# beacon_pcb.net
KiCad netlist of a schematic drawn in Altium Designer
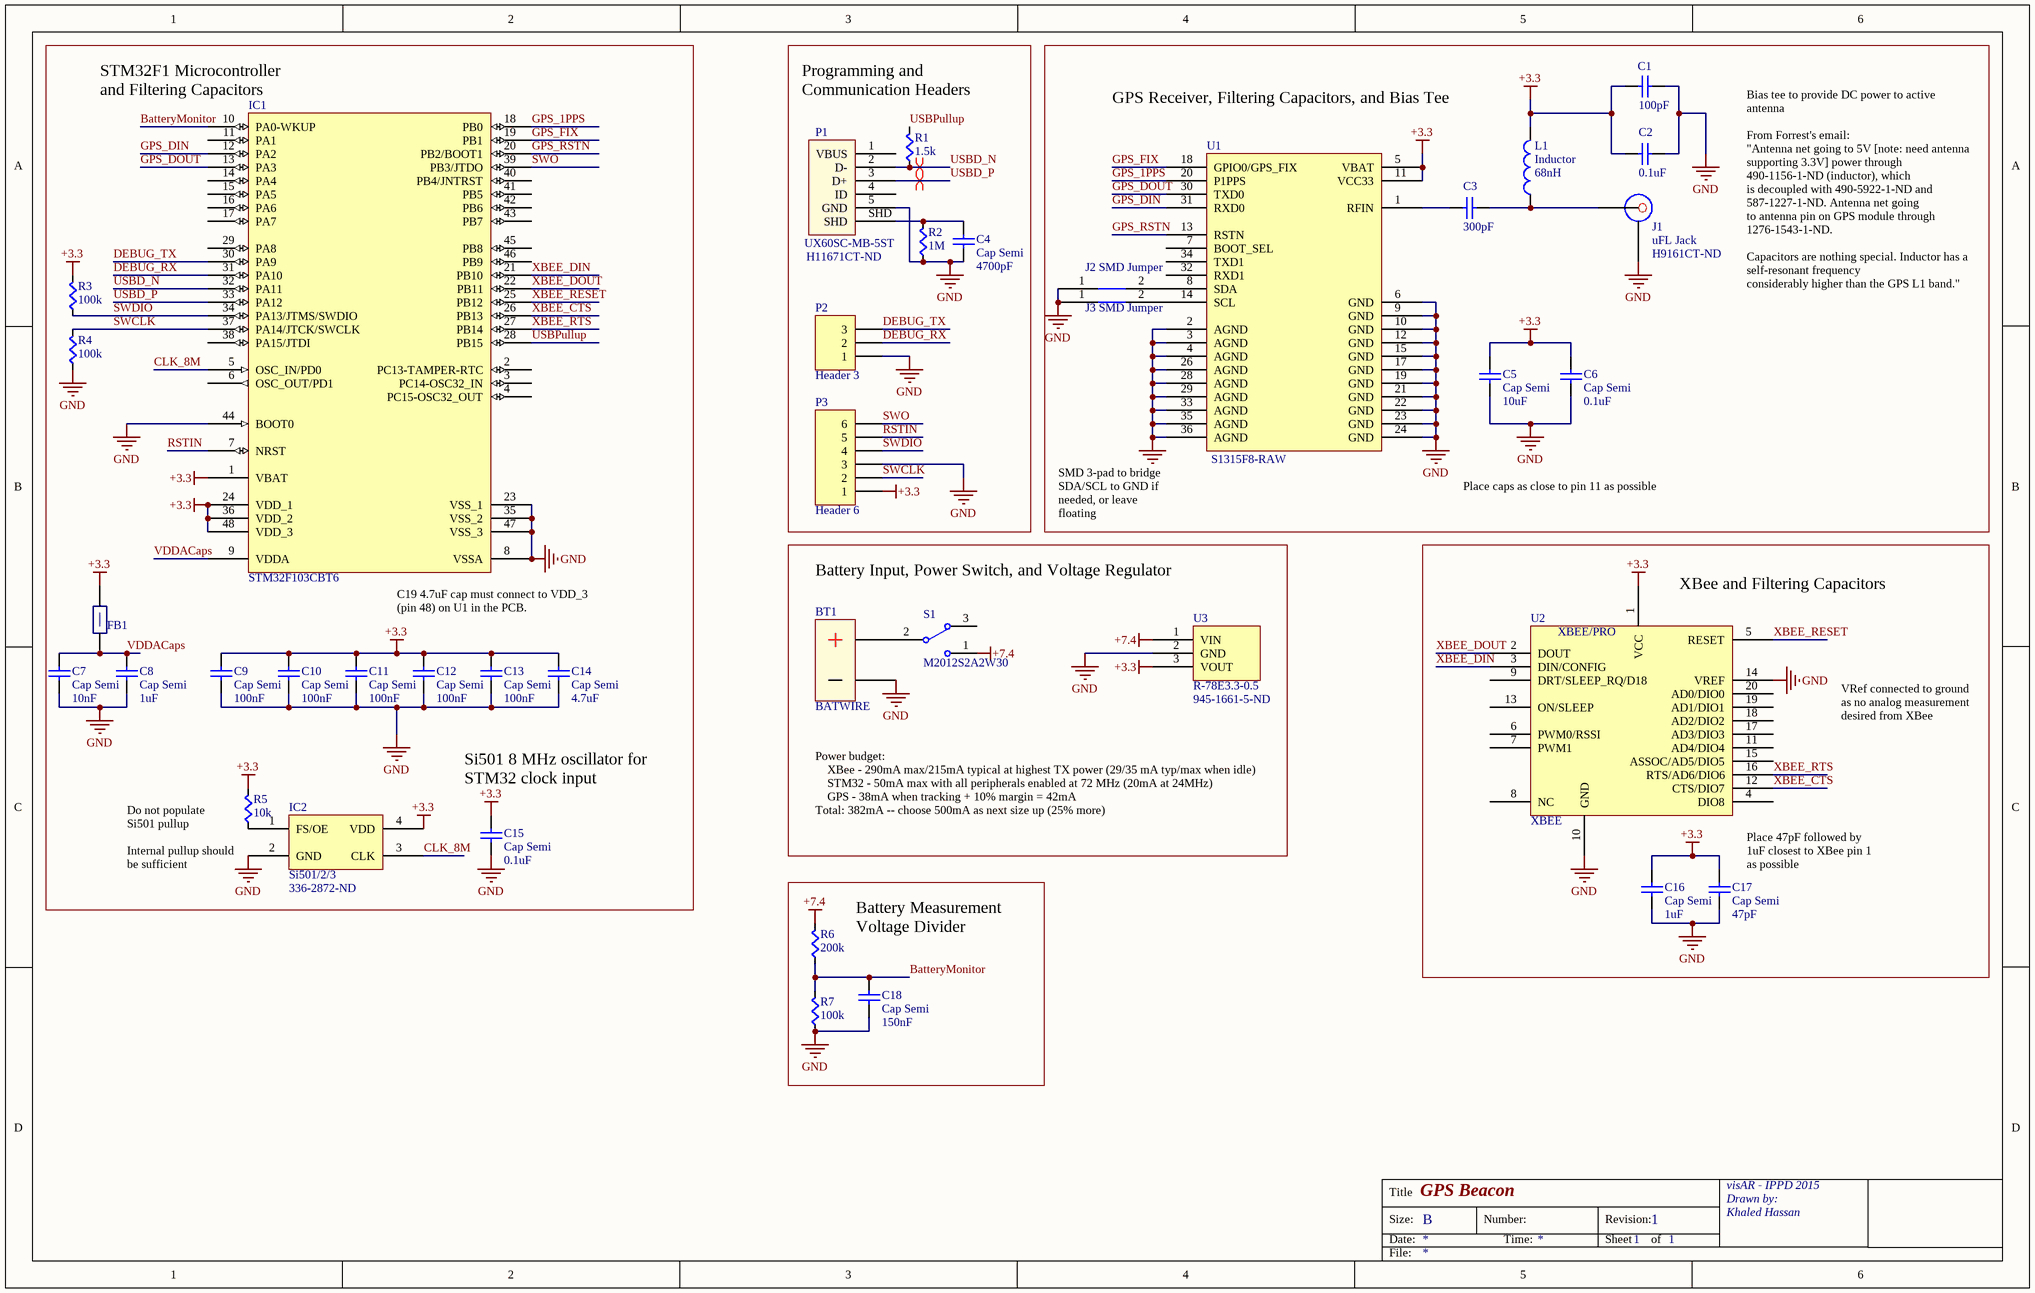
[diagram p0: beacon_pcb.SchDoc]

(export (version "E")
  (design (tool "Eeschema 10.0.6"))
  (components
    (comp (ref "BT1")
      (value "BATWIRE")
      (footprint "BATWIRE12")
      (description "Two large gauge leads soldered directly to the board.")
      (libsource (lib "Connectors") (part "BATWIRE"))
    )
    (comp (ref "C1")
      (value "100pF")
      (footprint "1608[0603]")
      (description "Capacitor (Semiconductor SIM Model)")
      (fields (field (name "Comment") "Cap Semi") (field (name "PUBLISHER") "Altium Limited"))
      (libsource (lib "Miscellaneous Devices") (part "Cap Semi"))
    )
    (comp (ref "C2")
      (value "0.1uF")
      (footprint "1608[0603]")
      (description "Capacitor (Semiconductor SIM Model)")
      (fields (field (name "Comment") "Cap Semi") (field (name "PUBLISHER") "Altium Limited"))
      (libsource (lib "Miscellaneous Devices") (part "Cap Semi"))
    )
    (comp (ref "C3")
      (value "300pF")
      (footprint "1608[0603]")
      (description "Capacitor (Semiconductor SIM Model)")
      (fields (field (name "Comment") "Cap Semi") (field (name "PUBLISHER") "Altium Limited"))
      (libsource (lib "Miscellaneous Devices") (part "Cap Semi"))
    )
    (comp (ref "C4")
      (value "Cap Semi")
      (footprint "1608[0603]")
      (description "Capacitor (Semiconductor SIM Model)")
      (fields (field (name "ALTIUM_VALUE") "4700pF") (field (name "PUBLISHER") "Altium Limited"))
      (libsource (lib "Miscellaneous Devices") (part "Cap Semi"))
    )
    (comp (ref "C5")
      (value "Cap Semi")
      (footprint "1608[0603]")
      (description "Capacitor (Semiconductor SIM Model)")
      (fields (field (name "ALTIUM_VALUE") "10uF") (field (name "PUBLISHER") "Altium Limited"))
      (libsource (lib "Miscellaneous Devices") (part "Cap Semi"))
    )
    (comp (ref "C6")
      (value "Cap Semi")
      (footprint "1608[0603]")
      (description "Capacitor (Semiconductor SIM Model)")
      (fields (field (name "ALTIUM_VALUE") "0.1uF") (field (name "PUBLISHER") "Altium Limited"))
      (libsource (lib "Miscellaneous Devices") (part "Cap Semi"))
    )
    (comp (ref "C7")
      (value "Cap Semi")
      (footprint "1608[0603]")
      (description "Capacitor (Semiconductor SIM Model)")
      (fields (field (name "ALTIUM_VALUE") "10nF") (field (name "PUBLISHER") "Altium Limited"))
      (libsource (lib "Miscellaneous Devices") (part "Cap Semi"))
    )
    (comp (ref "C8")
      (value "Cap Semi")
      (footprint "1608[0603]")
      (description "Capacitor (Semiconductor SIM Model)")
      (fields (field (name "ALTIUM_VALUE") "1uF") (field (name "PUBLISHER") "Altium Limited"))
      (libsource (lib "Miscellaneous Devices") (part "Cap Semi"))
    )
    (comp (ref "C9")
      (value "Cap Semi")
      (footprint "1608[0603]")
      (description "Capacitor (Semiconductor SIM Model)")
      (fields (field (name "ALTIUM_VALUE") "100nF") (field (name "PUBLISHER") "Altium Limited"))
      (libsource (lib "Miscellaneous Devices") (part "Cap Semi"))
    )
    (comp (ref "C10")
      (value "Cap Semi")
      (footprint "1608[0603]")
      (description "Capacitor (Semiconductor SIM Model)")
      (fields (field (name "ALTIUM_VALUE") "100nF") (field (name "PUBLISHER") "Altium Limited"))
      (libsource (lib "Miscellaneous Devices") (part "Cap Semi"))
    )
    (comp (ref "C11")
      (value "Cap Semi")
      (footprint "1608[0603]")
      (description "Capacitor (Semiconductor SIM Model)")
      (fields (field (name "ALTIUM_VALUE") "100nF") (field (name "PUBLISHER") "Altium Limited"))
      (libsource (lib "Miscellaneous Devices") (part "Cap Semi"))
    )
    (comp (ref "C12")
      (value "Cap Semi")
      (footprint "1608[0603]")
      (description "Capacitor (Semiconductor SIM Model)")
      (fields (field (name "ALTIUM_VALUE") "100nF") (field (name "PUBLISHER") "Altium Limited"))
      (libsource (lib "Miscellaneous Devices") (part "Cap Semi"))
    )
    (comp (ref "C13")
      (value "Cap Semi")
      (footprint "1608[0603]")
      (description "Capacitor (Semiconductor SIM Model)")
      (fields (field (name "ALTIUM_VALUE") "100nF") (field (name "PUBLISHER") "Altium Limited"))
      (libsource (lib "Miscellaneous Devices") (part "Cap Semi"))
    )
    (comp (ref "C14")
      (value "Cap Semi")
      (footprint "1608[0603]")
      (description "Capacitor (Semiconductor SIM Model)")
      (fields (field (name "ALTIUM_VALUE") "4.7uF") (field (name "PUBLISHER") "Altium Limited"))
      (libsource (lib "Miscellaneous Devices") (part "Cap Semi"))
    )
    (comp (ref "C15")
      (value "Cap Semi")
      (footprint "1608[0603]")
      (description "Capacitor (Semiconductor SIM Model)")
      (fields (field (name "ALTIUM_VALUE") "0.1uF") (field (name "PUBLISHER") "Altium Limited"))
      (libsource (lib "Miscellaneous Devices") (part "Cap Semi"))
    )
    (comp (ref "C16")
      (value "Cap Semi")
      (footprint "1608[0603]")
      (description "Capacitor (Semiconductor SIM Model)")
      (fields (field (name "ALTIUM_VALUE") "1uF") (field (name "PUBLISHER") "Altium Limited"))
      (libsource (lib "Miscellaneous Devices") (part "Cap Semi"))
    )
    (comp (ref "C17")
      (value "Cap Semi")
      (footprint "1608[0603]")
      (description "Capacitor (Semiconductor SIM Model)")
      (fields (field (name "ALTIUM_VALUE") "47pF") (field (name "PUBLISHER") "Altium Limited"))
      (libsource (lib "Miscellaneous Devices") (part "Cap Semi"))
    )
    (comp (ref "C18")
      (value "Cap Semi")
      (footprint "1608[0603]")
      (description "Capacitor (Semiconductor SIM Model)")
      (fields (field (name "ALTIUM_VALUE") "150nF") (field (name "PUBLISHER") "Altium Limited"))
      (libsource (lib "Miscellaneous Devices") (part "Cap Semi"))
    )
    (comp (ref "FB1")
      (value "FBead")
      (footprint "RES0603")
      (description "Ferrite Bead")
      (libsource (lib "Passives") (part "FBead"))
    )
    (comp (ref "IC1")
      (value "STM32F103CBT6")
      (footprint "STM-LQFP48_N")
      (description "STM32 ARM-based 32-bit MCU with 64 Kbytes Flash, 48-pin LQFP, Industrial Temperature")
      (fields (field (name "PUBLISHER") "Altium Limited"))
      (libsource (lib "ST Microcontroller 32-Bit STM32") (part "STM32F103C8T6"))
    )
    (comp (ref "IC2")
      (value "Si501/2/3")
      (footprint "3.2 x 5 mm 4-pin DFN")
      (fields (field (name "SUPPLIER PART NUMBER 1") "336-2872-ND"))
      (libsource (lib "beacon_pcb") (part "Si501/2/3"))
    )
    (comp (ref "J1")
      (value "uFL Jack")
      (footprint "H9161CT-ND")
      (fields (field (name "SUPPLIER PART NUMBER 1") "H9161CT-ND"))
      (libsource (lib "beacon_pcb") (part "uFL Jack"))
    )
    (comp (ref "J2")
      (value "SMD Jumper")
      (footprint "SMD 2PAD")
      (libsource (lib "beacon_pcb") (part "SMD Jumper"))
    )
    (comp (ref "J3")
      (value "SMD Jumper")
      (footprint "SMD 2PAD")
      (libsource (lib "beacon_pcb") (part "SMD Jumper"))
    )
    (comp (ref "L1")
      (value "Inductor")
      (footprint "0402-A")
      (fields (field (name "ALTIUM_VALUE") "68nH") (field (name "PUBLISHER") "Altium Limited"))
      (libsource (lib "Miscellaneous Devices") (part "Inductor"))
    )
    (comp (ref "P1")
      (value "UX60SC-MB-5ST")
      (footprint "UX60SC-MB-5ST")
      (description "USB Mini B Metal Shield SMT")
      (fields (field (name "SUPPLIER PART NUMBER 1") "H11671CT-ND"))
      (libsource (lib "Connectors") (part "UX60SC-MB-5ST"))
    )
    (comp (ref "P2")
      (value "Header 3")
      (footprint "HDR1X3")
      (description "Header, 3-Pin")
      (fields (field (name "PUBLISHER") "Altium Limited"))
      (libsource (lib "Miscellaneous Connectors") (part "Header 3"))
    )
    (comp (ref "P3")
      (value "Header 6")
      (footprint "HDR1X6")
      (description "Header, 6-Pin")
      (fields (field (name "PUBLISHER") "Altium Limited"))
      (libsource (lib "Miscellaneous Connectors") (part "Header 6"))
    )
    (comp (ref "R1")
      (value "1.5k")
      (footprint "RES0603")
      (fields (field (name "Comment") "Res"))
      (libsource (lib "Passives") (part "Res"))
    )
    (comp (ref "R2")
      (value "1M")
      (footprint "RES0603")
      (fields (field (name "Comment") "Res"))
      (libsource (lib "Passives") (part "Res"))
    )
    (comp (ref "R3")
      (value "100k")
      (footprint "RES0603")
      (fields (field (name "Comment") "Res"))
      (libsource (lib "Passives") (part "Res"))
    )
    (comp (ref "R4")
      (value "100k")
      (footprint "RES0603")
      (fields (field (name "Comment") "Res"))
      (libsource (lib "Passives") (part "Res"))
    )
    (comp (ref "R5")
      (value "10k")
      (footprint "RES0603")
      (fields (field (name "Comment") "Res"))
      (libsource (lib "Passives") (part "Res"))
    )
    (comp (ref "R6")
      (value "200k")
      (footprint "RES0603")
      (fields (field (name "Comment") "Res"))
      (libsource (lib "Passives") (part "Res"))
    )
    (comp (ref "R7")
      (value "100k")
      (footprint "RES0603")
      (fields (field (name "Comment") "Res"))
      (libsource (lib "Passives") (part "Res"))
    )
    (comp (ref "S1")
      (value "M2012S2A2W30")
      (footprint "M2012S2A2W30")
      (description "SPDT Subminiature Toggle Switch, Right Angle Mounting, Vertical Actuation")
      (fields (field (name "PUBLISHER") "Altium Limited"))
      (libsource (lib "Miscellaneous Devices") (part "SW-SPDT"))
    )
    (comp (ref "U1")
      (value "S1315F8-RAW")
      (footprint "S1315F8-RAW")
      (libsource (lib "beacon_pcb") (part "S1315F8-RAW"))
    )
    (comp (ref "U2") (value "XBEE") (footprint "XBEE/PRO") (libsource (lib "ECE Lib") (part "XBEE")))
    (comp (ref "U3")
      (value "R-78E3.3-0.5")
      (footprint "R-78E3.3-0.5")
      (fields (field (name "SUPPLIER PART NUMBER 1") "945-1661-5-ND"))
      (libsource (lib "beacon_pcb") (part "R-78E3.3-0.5"))
    )
  )
  (nets
    (net (code "1") (name "+3.3") (class "Default")
      (node (ref "C1") (pin "2") (pinfunction "2_2") (pintype "passive"))
      (node (ref "C10") (pin "2") (pinfunction "2_2") (pintype "passive"))
      (node (ref "C11") (pin "2") (pinfunction "2_2") (pintype "passive"))
      (node (ref "C12") (pin "2") (pinfunction "2_2") (pintype "passive"))
      (node (ref "C13") (pin "2") (pinfunction "2_2") (pintype "passive"))
      (node (ref "C14") (pin "2") (pinfunction "2_2") (pintype "passive"))
      (node (ref "C15") (pin "2") (pinfunction "2_2") (pintype "passive"))
      (node (ref "C16") (pin "2") (pinfunction "2_2") (pintype "passive"))
      (node (ref "C17") (pin "2") (pinfunction "2_2") (pintype "passive"))
      (node (ref "C2") (pin "2") (pinfunction "2_2") (pintype "passive"))
      (node (ref "C5") (pin "2") (pinfunction "2_2") (pintype "passive"))
      (node (ref "C6") (pin "2") (pinfunction "2_2") (pintype "passive"))
      (node (ref "C9") (pin "2") (pinfunction "2_2") (pintype "passive"))
      (node (ref "FB1") (pin "2") (pinfunction "B_2") (pintype "passive"))
      (node (ref "IC1") (pin "1") (pinfunction "VBAT_1") (pintype "power_in"))
      (node (ref "IC1") (pin "24") (pinfunction "VDD_1_24") (pintype "power_in"))
      (node (ref "IC1") (pin "36") (pinfunction "VDD_2_36") (pintype "power_in"))
      (node (ref "IC1") (pin "48") (pinfunction "VDD_3_48") (pintype "power_in"))
      (node (ref "IC2") (pin "4") (pinfunction "VDD_4") (pintype "passive"))
      (node (ref "L1") (pin "2") (pinfunction "2_2") (pintype "passive"))
      (node (ref "P3") (pin "1") (pinfunction "1_1") (pintype "passive"))
      (node (ref "R3") (pin "1") (pinfunction "A_1") (pintype "passive"))
      (node (ref "R5") (pin "1") (pinfunction "A_1") (pintype "passive"))
      (node (ref "U1") (pin "11") (pinfunction "VCC33_11") (pintype "passive"))
      (node (ref "U1") (pin "5") (pinfunction "VBAT_5") (pintype "passive"))
      (node (ref "U2") (pin "1") (pinfunction "VCC_1") (pintype "passive"))
      (node (ref "U3") (pin "3") (pinfunction "VOUT_3") (pintype "passive"))
    )
    (net (code "2") (name "+7.4") (class "Default")
      (node (ref "R6") (pin "1") (pinfunction "A_1") (pintype "passive"))
      (node (ref "S1") (pin "1") (pinfunction "1_1") (pintype "passive"))
      (node (ref "U3") (pin "1") (pinfunction "VIN_1") (pintype "passive"))
    )
    (net (code "3") (name "/BatteryMonitor") (class "Default")
      (node (ref "C18") (pin "2") (pinfunction "2_2") (pintype "passive"))
      (node (ref "IC1") (pin "10") (pinfunction "PA0-WKUP_10") (pintype "bidirectional"))
      (node (ref "R6") (pin "2") (pinfunction "B_2") (pintype "passive"))
      (node (ref "R7") (pin "1") (pinfunction "A_1") (pintype "passive"))
    )
    (net (code "4") (name "/CLK_8M") (class "Default")
      (node (ref "IC1") (pin "5") (pinfunction "OSC_IN/PD0_5") (pintype "input"))
      (node (ref "IC2") (pin "3") (pinfunction "CLK_3") (pintype "passive"))
    )
    (net (code "5") (name "/DEBUG_RX") (class "Default")
      (node (ref "IC1") (pin "31") (pinfunction "PA10_31") (pintype "bidirectional"))
      (node (ref "P2") (pin "2") (pinfunction "2_2") (pintype "passive"))
    )
    (net (code "6") (name "/DEBUG_TX") (class "Default")
      (node (ref "IC1") (pin "30") (pinfunction "PA9_30") (pintype "bidirectional"))
      (node (ref "P2") (pin "3") (pinfunction "3_3") (pintype "passive"))
    )
    (net (code "7") (name "/GPS_1PPS") (class "Default")
      (node (ref "IC1") (pin "18") (pinfunction "PB0_18") (pintype "bidirectional"))
      (node (ref "U1") (pin "20") (pinfunction "P1PPS_20") (pintype "passive"))
    )
    (net (code "8") (name "/GPS_DIN") (class "Default")
      (node (ref "IC1") (pin "12") (pinfunction "PA2_12") (pintype "bidirectional"))
      (node (ref "U1") (pin "31") (pinfunction "RXD0_31") (pintype "passive"))
    )
    (net (code "9") (name "/GPS_DOUT") (class "Default")
      (node (ref "IC1") (pin "13") (pinfunction "PA3_13") (pintype "bidirectional"))
      (node (ref "U1") (pin "30") (pinfunction "TXD0_30") (pintype "passive"))
    )
    (net (code "10") (name "/GPS_FIX") (class "Default")
      (node (ref "IC1") (pin "19") (pinfunction "PB1_19") (pintype "bidirectional"))
      (node (ref "U1") (pin "18") (pinfunction "GPIO0/GPS_FIX_18") (pintype "passive"))
    )
    (net (code "11") (name "/GPS_RSTN") (class "Default")
      (node (ref "IC1") (pin "20") (pinfunction "PB2/BOOT1_20") (pintype "bidirectional"))
      (node (ref "U1") (pin "13") (pinfunction "RSTN_13") (pintype "passive"))
    )
    (net (code "12") (name "/RSTIN") (class "Default")
      (node (ref "IC1") (pin "7") (pinfunction "NRST_7") (pintype "bidirectional"))
      (node (ref "P3") (pin "5") (pinfunction "5_5") (pintype "passive"))
    )
    (net (code "13") (name "/SWCLK") (class "Default")
      (node (ref "IC1") (pin "37") (pinfunction "PA14/JTCK/SWCLK_37") (pintype "bidirectional"))
      (node (ref "P3") (pin "2") (pinfunction "2_2") (pintype "passive"))
      (node (ref "R4") (pin "1") (pinfunction "A_1") (pintype "passive"))
    )
    (net (code "14") (name "/SWDIO") (class "Default")
      (node (ref "IC1") (pin "34") (pinfunction "PA13/JTMS/SWDIO_34") (pintype "bidirectional"))
      (node (ref "P3") (pin "4") (pinfunction "4_4") (pintype "passive"))
      (node (ref "R3") (pin "2") (pinfunction "B_2") (pintype "passive"))
    )
    (net (code "15") (name "/SWO") (class "Default")
      (node (ref "IC1") (pin "39") (pinfunction "PB3/JTDO_39") (pintype "bidirectional"))
      (node (ref "P3") (pin "6") (pinfunction "6_6") (pintype "passive"))
    )
    (net (code "16") (name "/USBD_N") (class "Default")
      (node (ref "IC1") (pin "32") (pinfunction "PA11_32") (pintype "bidirectional"))
      (node (ref "P1") (pin "2") (pinfunction "D-_2") (pintype "passive"))
      (node (ref "R1") (pin "2") (pinfunction "B_2") (pintype "passive"))
    )
    (net (code "17") (name "/USBD_P") (class "Default")
      (node (ref "IC1") (pin "33") (pinfunction "PA12_33") (pintype "bidirectional"))
      (node (ref "P1") (pin "3") (pinfunction "D+_3") (pintype "passive"))
    )
    (net (code "18") (name "/USBPullup") (class "Default")
      (node (ref "IC1") (pin "28") (pinfunction "PB15_28") (pintype "bidirectional"))
      (node (ref "R1") (pin "1") (pinfunction "A_1") (pintype "passive"))
    )
    (net (code "19") (name "/VDDACaps") (class "Default")
      (node (ref "C7") (pin "2") (pinfunction "2_2") (pintype "passive"))
      (node (ref "C8") (pin "2") (pinfunction "2_2") (pintype "passive"))
      (node (ref "FB1") (pin "1") (pinfunction "A_1") (pintype "passive"))
      (node (ref "IC1") (pin "9") (pinfunction "VDDA_9") (pintype "power_in"))
    )
    (net (code "20") (name "/XBEE_CTS") (class "Default")
      (node (ref "IC1") (pin "26") (pinfunction "PB13_26") (pintype "bidirectional"))
      (node (ref "U2") (pin "12") (pinfunction "CTS/DIO7_12") (pintype "passive"))
    )
    (net (code "21") (name "/XBEE_DIN") (class "Default")
      (node (ref "IC1") (pin "21") (pinfunction "PB10_21") (pintype "bidirectional"))
      (node (ref "U2") (pin "3") (pinfunction "DIN/CONFIG_3") (pintype "passive"))
    )
    (net (code "22") (name "/XBEE_DOUT") (class "Default")
      (node (ref "IC1") (pin "22") (pinfunction "PB11_22") (pintype "bidirectional"))
      (node (ref "U2") (pin "2") (pinfunction "DOUT_2") (pintype "passive"))
    )
    (net (code "23") (name "/XBEE_RESET") (class "Default")
      (node (ref "IC1") (pin "25") (pinfunction "PB12_25") (pintype "bidirectional"))
      (node (ref "U2") (pin "5") (pinfunction "RESET_5") (pintype "passive"))
    )
    (net (code "24") (name "/XBEE_RTS") (class "Default")
      (node (ref "IC1") (pin "27") (pinfunction "PB14_27") (pintype "bidirectional"))
      (node (ref "U2") (pin "16") (pinfunction "RTS/AD6/DIO6_16") (pintype "passive"))
    )
    (net (code "25") (name "GND") (class "Default")
      (node (ref "BT1") (pin "-") (pinfunction "-_-") (pintype "power_in"))
      (node (ref "C1") (pin "1") (pinfunction "1_1") (pintype "passive"))
      (node (ref "C10") (pin "1") (pinfunction "1_1") (pintype "passive"))
      (node (ref "C11") (pin "1") (pinfunction "1_1") (pintype "passive"))
      (node (ref "C12") (pin "1") (pinfunction "1_1") (pintype "passive"))
      (node (ref "C13") (pin "1") (pinfunction "1_1") (pintype "passive"))
      (node (ref "C14") (pin "1") (pinfunction "1_1") (pintype "passive"))
      (node (ref "C15") (pin "1") (pinfunction "1_1") (pintype "passive"))
      (node (ref "C16") (pin "1") (pinfunction "1_1") (pintype "passive"))
      (node (ref "C17") (pin "1") (pinfunction "1_1") (pintype "passive"))
      (node (ref "C18") (pin "1") (pinfunction "1_1") (pintype "passive"))
      (node (ref "C2") (pin "1") (pinfunction "1_1") (pintype "passive"))
      (node (ref "C4") (pin "1") (pinfunction "1_1") (pintype "passive"))
      (node (ref "C5") (pin "1") (pinfunction "1_1") (pintype "passive"))
      (node (ref "C6") (pin "1") (pinfunction "1_1") (pintype "passive"))
      (node (ref "C7") (pin "1") (pinfunction "1_1") (pintype "passive"))
      (node (ref "C8") (pin "1") (pinfunction "1_1") (pintype "passive"))
      (node (ref "C9") (pin "1") (pinfunction "1_1") (pintype "passive"))
      (node (ref "IC1") (pin "23") (pinfunction "VSS_1_23") (pintype "power_in"))
      (node (ref "IC1") (pin "35") (pinfunction "VSS_2_35") (pintype "power_in"))
      (node (ref "IC1") (pin "44") (pinfunction "BOOT0_44") (pintype "input"))
      (node (ref "IC1") (pin "47") (pinfunction "VSS_3_47") (pintype "power_in"))
      (node (ref "IC1") (pin "8") (pinfunction "VSSA_8") (pintype "power_in"))
      (node (ref "IC2") (pin "2") (pinfunction "GND_2") (pintype "passive"))
      (node (ref "J1") (pin "GND") (pinfunction "GND_GND") (pintype "passive"))
      (node (ref "J2") (pin "1") (pintype "passive"))
      (node (ref "J3") (pin "1") (pintype "passive"))
      (node (ref "P1") (pin "5") (pinfunction "GND_5") (pintype "passive"))
      (node (ref "P2") (pin "1") (pinfunction "1_1") (pintype "passive"))
      (node (ref "P3") (pin "3") (pinfunction "3_3") (pintype "passive"))
      (node (ref "R2") (pin "2") (pinfunction "B_2") (pintype "passive"))
      (node (ref "R4") (pin "2") (pinfunction "B_2") (pintype "passive"))
      (node (ref "R7") (pin "2") (pinfunction "B_2") (pintype "passive"))
      (node (ref "U1") (pin "10") (pinfunction "GND_10") (pintype "passive"))
      (node (ref "U1") (pin "12") (pinfunction "GND_12") (pintype "passive"))
      (node (ref "U1") (pin "15") (pinfunction "GND_15") (pintype "passive"))
      (node (ref "U1") (pin "17") (pinfunction "GND_17") (pintype "passive"))
      (node (ref "U1") (pin "19") (pinfunction "GND_19") (pintype "passive"))
      (node (ref "U1") (pin "2") (pinfunction "AGND_2") (pintype "passive"))
      (node (ref "U1") (pin "21") (pinfunction "GND_21") (pintype "passive"))
      (node (ref "U1") (pin "22") (pinfunction "GND_22") (pintype "passive"))
      (node (ref "U1") (pin "23") (pinfunction "GND_23") (pintype "passive"))
      (node (ref "U1") (pin "24") (pinfunction "GND_24") (pintype "passive"))
      (node (ref "U1") (pin "26") (pinfunction "AGND_26") (pintype "passive"))
      (node (ref "U1") (pin "28") (pinfunction "AGND_28") (pintype "passive"))
      (node (ref "U1") (pin "29") (pinfunction "AGND_29") (pintype "passive"))
      (node (ref "U1") (pin "3") (pinfunction "AGND_3") (pintype "passive"))
      (node (ref "U1") (pin "33") (pinfunction "AGND_33") (pintype "passive"))
      (node (ref "U1") (pin "35") (pinfunction "AGND_35") (pintype "passive"))
      (node (ref "U1") (pin "36") (pinfunction "AGND_36") (pintype "passive"))
      (node (ref "U1") (pin "4") (pinfunction "AGND_4") (pintype "passive"))
      (node (ref "U1") (pin "6") (pinfunction "GND_6") (pintype "passive"))
      (node (ref "U1") (pin "9") (pinfunction "GND_9") (pintype "passive"))
      (node (ref "U2") (pin "10") (pinfunction "GND_10") (pintype "passive"))
      (node (ref "U2") (pin "14") (pinfunction "VREF_14") (pintype "passive"))
      (node (ref "U3") (pin "2") (pinfunction "GND_2") (pintype "passive"))
    )
    (net (code "26") (name "Net-(BT1-Pad+)") (class "Default")
      (node (ref "BT1") (pin "+") (pinfunction "+_+") (pintype "power_in"))
      (node (ref "S1") (pin "2") (pinfunction "2_2") (pintype "passive"))
    )
    (net (code "27") (name "Net-(C3-Pad1)") (class "Default")
      (node (ref "C3") (pin "1") (pinfunction "1_1") (pintype "passive"))
      (node (ref "J1") (pin "SIG") (pinfunction "SIG_SIG") (pintype "passive"))
      (node (ref "L1") (pin "1") (pinfunction "1_1") (pintype "passive"))
    )
    (net (code "28") (name "Net-(IC2-FS{slash}OE)") (class "Default")
      (node (ref "IC2") (pin "1") (pinfunction "FS/OE_1") (pintype "passive"))
      (node (ref "R5") (pin "2") (pinfunction "B_2") (pintype "passive"))
    )
    (net (code "29") (name "Net-(R2-A)") (class "Default")
      (node (ref "C4") (pin "2") (pinfunction "2_2") (pintype "passive"))
      (node (ref "P1") (pin "SHD") (pinfunction "SHD_SHD") (pintype "passive"))
      (node (ref "R2") (pin "1") (pinfunction "A_1") (pintype "passive"))
    )
    (net (code "30") (name "Net-(U1-RFIN)") (class "Default")
      (node (ref "C3") (pin "2") (pinfunction "2_2") (pintype "passive"))
      (node (ref "U1") (pin "1") (pinfunction "RFIN_1") (pintype "passive"))
    )
    (net (code "31") (name "Net-(U1-SCL)") (class "Default")
      (node (ref "J3") (pin "2") (pintype "passive"))
      (node (ref "U1") (pin "14") (pinfunction "SCL_14") (pintype "passive"))
    )
    (net (code "32") (name "Net-(U1-SDA)") (class "Default")
      (node (ref "J2") (pin "2") (pintype "passive"))
      (node (ref "U1") (pin "8") (pinfunction "SDA_8") (pintype "passive"))
    )
    (net (code "33") (name "unconnected-(IC1-OSC_OUT{slash}PD1-Pad6)") (class "Default")
      (node (ref "IC1") (pin "6") (pinfunction "OSC_OUT/PD1_6") (pintype "output"))
    )
    (net (code "34") (name "unconnected-(IC1-PA1-Pad11)") (class "Default")
      (node (ref "IC1") (pin "11") (pinfunction "PA1_11") (pintype "bidirectional"))
    )
    (net (code "35") (name "unconnected-(IC1-PA4-Pad14)") (class "Default")
      (node (ref "IC1") (pin "14") (pinfunction "PA4_14") (pintype "bidirectional"))
    )
    (net (code "36") (name "unconnected-(IC1-PA5-Pad15)") (class "Default")
      (node (ref "IC1") (pin "15") (pinfunction "PA5_15") (pintype "bidirectional"))
    )
    (net (code "37") (name "unconnected-(IC1-PA6-Pad16)") (class "Default")
      (node (ref "IC1") (pin "16") (pinfunction "PA6_16") (pintype "bidirectional"))
    )
    (net (code "38") (name "unconnected-(IC1-PA7-Pad17)") (class "Default")
      (node (ref "IC1") (pin "17") (pinfunction "PA7_17") (pintype "bidirectional"))
    )
    (net (code "39") (name "unconnected-(IC1-PA8-Pad29)") (class "Default")
      (node (ref "IC1") (pin "29") (pinfunction "PA8_29") (pintype "bidirectional"))
    )
    (net (code "40") (name "unconnected-(IC1-PA15{slash}JTDI-Pad38)") (class "Default")
      (node (ref "IC1") (pin "38") (pinfunction "PA15/JTDI_38") (pintype "bidirectional"))
    )
    (net (code "41") (name "unconnected-(IC1-PB4{slash}JNTRST-Pad40)") (class "Default")
      (node (ref "IC1") (pin "40") (pinfunction "PB4/JNTRST_40") (pintype "bidirectional"))
    )
    (net (code "42") (name "unconnected-(IC1-PB5-Pad41)") (class "Default")
      (node (ref "IC1") (pin "41") (pinfunction "PB5_41") (pintype "bidirectional"))
    )
    (net (code "43") (name "unconnected-(IC1-PB6-Pad42)") (class "Default")
      (node (ref "IC1") (pin "42") (pinfunction "PB6_42") (pintype "bidirectional"))
    )
    (net (code "44") (name "unconnected-(IC1-PB7-Pad43)") (class "Default")
      (node (ref "IC1") (pin "43") (pinfunction "PB7_43") (pintype "bidirectional"))
    )
    (net (code "45") (name "unconnected-(IC1-PB8-Pad45)") (class "Default")
      (node (ref "IC1") (pin "45") (pinfunction "PB8_45") (pintype "bidirectional"))
    )
    (net (code "46") (name "unconnected-(IC1-PB9-Pad46)") (class "Default")
      (node (ref "IC1") (pin "46") (pinfunction "PB9_46") (pintype "bidirectional"))
    )
    (net (code "47") (name "unconnected-(IC1-PC13-TAMPER-RTC-Pad2)") (class "Default")
      (node (ref "IC1") (pin "2") (pinfunction "PC13-TAMPER-RTC_2") (pintype "bidirectional"))
    )
    (net (code "48") (name "unconnected-(IC1-PC14-OSC32_IN-Pad3)") (class "Default")
      (node (ref "IC1") (pin "3") (pinfunction "PC14-OSC32_IN_3") (pintype "bidirectional"))
    )
    (net (code "49") (name "unconnected-(IC1-PC15-OSC32_OUT-Pad4)") (class "Default")
      (node (ref "IC1") (pin "4") (pinfunction "PC15-OSC32_OUT_4") (pintype "bidirectional"))
    )
    (net (code "50") (name "unconnected-(P1-ID-Pad4)") (class "Default")
      (node (ref "P1") (pin "4") (pinfunction "ID_4") (pintype "passive"))
    )
    (net (code "51") (name "unconnected-(P1-VBUS-Pad1)") (class "Default")
      (node (ref "P1") (pin "1") (pinfunction "VBUS_1") (pintype "passive"))
    )
    (net (code "52") (name "unconnected-(S1-Pad3)") (class "Default")
      (node (ref "S1") (pin "3") (pinfunction "3_3") (pintype "passive"))
    )
    (net (code "53") (name "unconnected-(U1-BOOT_SEL-Pad7)") (class "Default")
      (node (ref "U1") (pin "7") (pinfunction "BOOT_SEL_7") (pintype "passive"))
    )
    (net (code "54") (name "unconnected-(U1-RXD1-Pad32)") (class "Default")
      (node (ref "U1") (pin "32") (pinfunction "RXD1_32") (pintype "passive"))
    )
    (net (code "55") (name "unconnected-(U1-TXD1-Pad34)") (class "Default")
      (node (ref "U1") (pin "34") (pinfunction "TXD1_34") (pintype "passive"))
    )
    (net (code "56") (name "unconnected-(U2-AD0{slash}DIO0-Pad20)") (class "Default")
      (node (ref "U2") (pin "20") (pinfunction "AD0/DIO0_20") (pintype "passive"))
    )
    (net (code "57") (name "unconnected-(U2-AD1{slash}DIO1-Pad19)") (class "Default")
      (node (ref "U2") (pin "19") (pinfunction "AD1/DIO1_19") (pintype "passive"))
    )
    (net (code "58") (name "unconnected-(U2-AD2{slash}DIO2-Pad18)") (class "Default")
      (node (ref "U2") (pin "18") (pinfunction "AD2/DIO2_18") (pintype "passive"))
    )
    (net (code "59") (name "unconnected-(U2-AD3{slash}DIO3-Pad17)") (class "Default")
      (node (ref "U2") (pin "17") (pinfunction "AD3/DIO3_17") (pintype "passive"))
    )
    (net (code "60") (name "unconnected-(U2-AD4{slash}DIO4-Pad11)") (class "Default")
      (node (ref "U2") (pin "11") (pinfunction "AD4/DIO4_11") (pintype "passive"))
    )
    (net (code "61") (name "unconnected-(U2-ASSOC{slash}AD5{slash}DIO5-Pad15)") (class "Default")
      (node (ref "U2") (pin "15") (pinfunction "ASSOC/AD5/DIO5_15") (pintype "passive"))
    )
    (net (code "62") (name "unconnected-(U2-DIO8-Pad4)") (class "Default")
      (node (ref "U2") (pin "4") (pinfunction "DIO8_4") (pintype "passive"))
    )
    (net (code "63") (name "unconnected-(U2-DRT{slash}SLEEP_RQ{slash}D18-Pad9)") (class "Default")
      (node (ref "U2") (pin "9") (pinfunction "DRT/SLEEP_RQ/D18_9") (pintype "passive"))
    )
    (net (code "64") (name "unconnected-(U2-NC-Pad8)") (class "Default")
      (node (ref "U2") (pin "8") (pinfunction "NC_8") (pintype "passive"))
    )
    (net (code "65") (name "unconnected-(U2-ON{slash}SLEEP-Pad13)") (class "Default")
      (node (ref "U2") (pin "13") (pinfunction "ON/SLEEP_13") (pintype "passive"))
    )
    (net (code "66") (name "unconnected-(U2-PWM0{slash}RSSI-Pad6)") (class "Default")
      (node (ref "U2") (pin "6") (pinfunction "PWM0/RSSI_6") (pintype "passive"))
    )
    (net (code "67") (name "unconnected-(U2-PWM1-Pad7)") (class "Default")
      (node (ref "U2") (pin "7") (pinfunction "PWM1_7") (pintype "passive"))
    )
  )
)
